# LightingUPS_v4-1.net
KiCad netlist of a schematic drawn in EAGLE
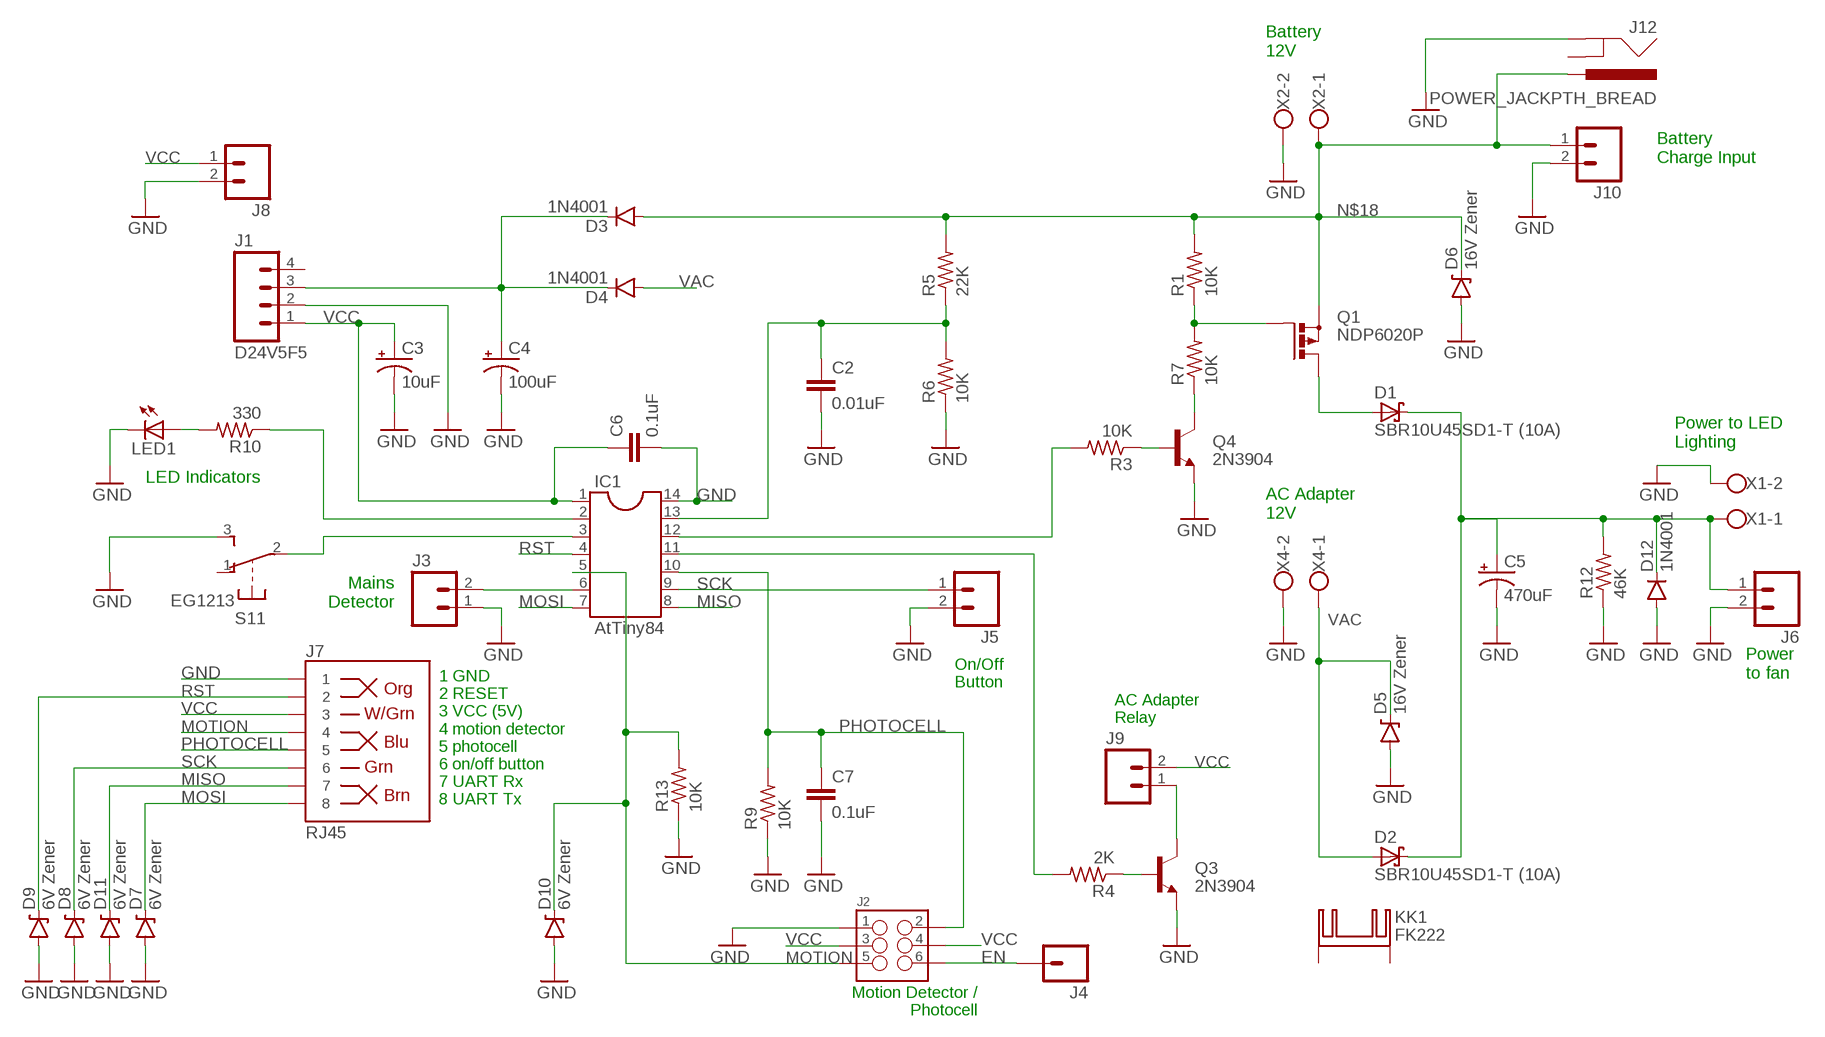
[diagram p0: schematic, sheet 1]

(export (version "E")
  (design (tool "Eeschema 10.0.6"))
  (components
    (comp (ref "C2")
      (value "0.01uF")
      (footprint "eagle-import:CAP-PTH-5MM")
      (libsource (lib "eagle-import") (part "SparkFun-Passives_CAPPTH1"))
    )
    (comp (ref "C3")
      (value "10uF")
      (footprint "eagle-import:CPOL-RADIAL-100UF-25V")
      (libsource (lib "eagle-import") (part "CAP_POLPTH1"))
    )
    (comp (ref "C4")
      (value "100uF")
      (footprint "eagle-import:CPOL-RADIAL-100UF-25V")
      (libsource (lib "eagle-import") (part "CAP_POLPTH1"))
    )
    (comp (ref "C5")
      (value "470uF")
      (footprint "eagle-import:CPOL-RADIAL-1000UF-25V")
      (libsource (lib "eagle-import") (part "CAP_POLPTH4"))
    )
    (comp (ref "C6")
      (value "0.1uF")
      (footprint "eagle-import:CAP-PTH-SMALL")
      (libsource (lib "eagle-import") (part "CAPPTH"))
    )
    (comp (ref "C7")
      (value "0.1uF")
      (footprint "eagle-import:CAP-PTH-SMALL")
      (libsource (lib "eagle-import") (part "CAPPTH"))
    )
    (comp (ref "D1")
      (value "SBR10U45SD1-T (10A)")
      (footprint "eagle-import:DO201T15")
      (libsource (lib "eagle-import") (part "SCHOTTKY-DIODEDO201T15"))
    )
    (comp (ref "D2")
      (value "SBR10U45SD1-T (10A)")
      (footprint "eagle-import:DO201T15")
      (libsource (lib "eagle-import") (part "SCHOTTKY-DIODEDO201T15"))
    )
    (comp (ref "D3")
      (value "1N4001")
      (footprint "eagle-import:DIODE-1N4001")
      (libsource (lib "eagle-import") (part "DIODEPTH"))
    )
    (comp (ref "D4")
      (value "1N4001")
      (footprint "eagle-import:DIODE-1N4001")
      (libsource (lib "eagle-import") (part "DIODEPTH"))
    )
    (comp (ref "D5")
      (value "16V Zener")
      (footprint "eagle-import:DIODE-ZENER")
      (libsource (lib "eagle-import") (part "DIODE-ZENERPTH"))
    )
    (comp (ref "D6")
      (value "16V Zener")
      (footprint "eagle-import:DIODE-ZENER")
      (libsource (lib "eagle-import") (part "DIODE-ZENERPTH"))
    )
    (comp (ref "D7")
      (value "6V Zener")
      (footprint "eagle-import:DIODE-ZENER")
      (libsource (lib "eagle-import") (part "DIODE-ZENERPTH"))
    )
    (comp (ref "D8")
      (value "6V Zener")
      (footprint "eagle-import:DIODE-ZENER")
      (libsource (lib "eagle-import") (part "DIODE-ZENERPTH"))
    )
    (comp (ref "D9")
      (value "6V Zener")
      (footprint "eagle-import:DIODE-ZENER")
      (libsource (lib "eagle-import") (part "DIODE-ZENERPTH"))
    )
    (comp (ref "D10")
      (value "6V Zener")
      (footprint "eagle-import:DIODE-ZENER")
      (libsource (lib "eagle-import") (part "DIODE-ZENERPTH"))
    )
    (comp (ref "D11")
      (value "6V Zener")
      (footprint "eagle-import:DIODE-ZENER")
      (libsource (lib "eagle-import") (part "DIODE-ZENERPTH"))
    )
    (comp (ref "D12")
      (value "1N4001")
      (footprint "eagle-import:DIODE-1N4001")
      (libsource (lib "eagle-import") (part "DIODEPTH"))
    )
    (comp (ref "IC1")
      (value "AtTiny84")
      (footprint "eagle-import:DIL14")
      (libsource (lib "eagle-import") (part "DIL14"))
    )
    (comp (ref "J1")
      (value "D24V5F5")
      (footprint "eagle-import:1X04")
      (libsource (lib "eagle-import") (part "M04PTH"))
    )
    (comp (ref "J2")
      (value "M03X2SHROUD")
      (footprint "eagle-import:2X3-SHROUDED")
      (libsource (lib "eagle-import") (part "M03X2SHROUD"))
    )
    (comp (ref "J3")
      (value "M02PTH")
      (footprint "eagle-import:1X02")
      (libsource (lib "eagle-import") (part "M02PTH"))
    )
    (comp (ref "J4")
      (value "M01PTH")
      (footprint "eagle-import:1X01")
      (libsource (lib "eagle-import") (part "M01PTH"))
    )
    (comp (ref "J5")
      (value "M02PTH")
      (footprint "eagle-import:1X02")
      (libsource (lib "eagle-import") (part "M02PTH"))
    )
    (comp (ref "J6")
      (value "M02PTH")
      (footprint "eagle-import:1X02")
      (libsource (lib "eagle-import") (part "M02PTH"))
    )
    (comp (ref "J7")
      (value "RJ45")
      (footprint "eagle-import:RJ45-8")
      (libsource (lib "eagle-import") (part "RJ45-8PTH"))
    )
    (comp (ref "J8")
      (value "M02PTH")
      (footprint "eagle-import:1X02")
      (libsource (lib "eagle-import") (part "M02PTH"))
    )
    (comp (ref "J9")
      (value "M02PTH")
      (footprint "eagle-import:1X02")
      (libsource (lib "eagle-import") (part "M02PTH"))
    )
    (comp (ref "J10")
      (value "M02PTH")
      (footprint "eagle-import:1X02")
      (libsource (lib "eagle-import") (part "M02PTH"))
    )
    (comp (ref "J12")
      (value "POWER_JACKPTH_BREAD")
      (footprint "eagle-import:POWER_JACK_PTH_BREAD")
      (libsource (lib "eagle-import") (part "POWER_JACKPTH_BREAD"))
    )
    (comp (ref "KK1")
      (value "FK222")
      (footprint "eagle-import:FK222")
      (libsource (lib "eagle-import") (part "FK222"))
    )
    (comp (ref "LED1")
      (value "LED5MM")
      (footprint "eagle-import:LED5MM")
      (libsource (lib "eagle-import") (part "LED5MM"))
    )
    (comp (ref "Q1")
      (value "NDP6020P")
      (footprint "eagle-import:TO220BV")
      (libsource (lib "eagle-import") (part "PMOSFET_PTO220BV"))
    )
    (comp (ref "Q3")
      (value "2N3904")
      (footprint "eagle-import:TO-92-AMMO")
      (libsource (lib "eagle-import") (part "TRANSISTOR_NPNTO-92-AMMO"))
    )
    (comp (ref "Q4")
      (value "2N3904")
      (footprint "eagle-import:TO-92-AMMO")
      (libsource (lib "eagle-import") (part "TRANSISTOR_NPNTO-92-AMMO"))
    )
    (comp (ref "R1")
      (value "10K")
      (footprint "eagle-import:0204_5")
      (libsource (lib "eagle-import") (part "R-US_0204/5"))
    )
    (comp (ref "R3")
      (value "10K")
      (footprint "eagle-import:0204_5")
      (libsource (lib "eagle-import") (part "R-US_0204/5"))
    )
    (comp (ref "R4")
      (value "2K")
      (footprint "eagle-import:0204_5")
      (libsource (lib "eagle-import") (part "R-US_0204/5"))
    )
    (comp (ref "R5")
      (value "22K")
      (footprint "eagle-import:0204_5")
      (libsource (lib "eagle-import") (part "R-US_0204/5"))
    )
    (comp (ref "R6")
      (value "10K")
      (footprint "eagle-import:0204_5")
      (libsource (lib "eagle-import") (part "R-US_0204/5"))
    )
    (comp (ref "R7")
      (value "10K")
      (footprint "eagle-import:0204_5")
      (libsource (lib "eagle-import") (part "R-US_0204/5"))
    )
    (comp (ref "R9")
      (value "10K")
      (footprint "eagle-import:0204_5")
      (libsource (lib "eagle-import") (part "R-US_0204/5"))
    )
    (comp (ref "R10")
      (value "330")
      (footprint "eagle-import:0204_5")
      (libsource (lib "eagle-import") (part "R-US_0204/5"))
    )
    (comp (ref "R12")
      (value "46K")
      (footprint "eagle-import:0204_5")
      (libsource (lib "eagle-import") (part "R-US_0204/5"))
    )
    (comp (ref "R13")
      (value "10K")
      (footprint "eagle-import:0204_5")
      (libsource (lib "eagle-import") (part "R-US_0204/5"))
    )
    (comp (ref "S1")
      (value "EG1213")
      (footprint "eagle-import:EG1213")
      (libsource (lib "eagle-import") (part "EG1213"))
    )
    (comp (ref "X1")
      (value "W237-102")
      (footprint "eagle-import:W237-102")
      (fields (field (name "MPN") "237-102"))
      (libsource (lib "eagle-import") (part "W237-102"))
    )
    (comp (ref "X2")
      (value "W237-102")
      (footprint "eagle-import:W237-102")
      (fields (field (name "MPN") "237-102"))
      (libsource (lib "eagle-import") (part "W237-102"))
    )
    (comp (ref "X4")
      (value "W237-102")
      (footprint "eagle-import:W237-102")
      (fields (field (name "MPN") "237-102"))
      (libsource (lib "eagle-import") (part "W237-102"))
    )
  )
  (nets
    (net (code "1") (name "/EN") (class "Default")
      (node (ref "J2") (pin "6") (pinfunction "6_6") (pintype "bidirectional"))
      (node (ref "J4") (pin "1") (pinfunction "1_1") (pintype "passive"))
    )
    (net (code "2") (name "/MISO") (class "Default")
      (node (ref "D11") (pin "P$1") (pinfunction "C_P$1") (pintype "passive"))
      (node (ref "IC1") (pin "8") (pinfunction "8_8") (pintype "passive"))
      (node (ref "J7") (pin "7") (pinfunction "7_7") (pintype "bidirectional"))
    )
    (net (code "3") (name "/MOSI") (class "Default")
      (node (ref "D7") (pin "P$1") (pinfunction "C_P$1") (pintype "passive"))
      (node (ref "IC1") (pin "7") (pinfunction "7_7") (pintype "passive"))
      (node (ref "J7") (pin "8") (pinfunction "8_8") (pintype "bidirectional"))
    )
    (net (code "4") (name "/MOTION") (class "Default")
      (node (ref "D10") (pin "P$1") (pinfunction "C_P$1") (pintype "passive"))
      (node (ref "IC1") (pin "5") (pinfunction "5_5") (pintype "passive"))
      (node (ref "J2") (pin "5") (pinfunction "5_5") (pintype "bidirectional"))
      (node (ref "J7") (pin "4") (pinfunction "4_4") (pintype "bidirectional"))
      (node (ref "R13") (pin "2") (pinfunction "2_2") (pintype "passive"))
    )
    (net (code "5") (name "/N$18") (class "Default")
      (node (ref "D3") (pin "A") (pinfunction "A_A") (pintype "passive"))
      (node (ref "D6") (pin "P$1") (pinfunction "C_P$1") (pintype "passive"))
      (node (ref "J10") (pin "1") (pinfunction "1_1") (pintype "passive"))
      (node (ref "J12") (pin "PWR") (pinfunction "PWR_PWR") (pintype "bidirectional"))
      (node (ref "Q1") (pin "S") (pinfunction "S_S") (pintype "passive"))
      (node (ref "R1") (pin "2") (pinfunction "2_2") (pintype "passive"))
      (node (ref "R5") (pin "2") (pinfunction "2_2") (pintype "passive"))
      (node (ref "X2") (pin "1") (pinfunction "KL_1") (pintype "passive"))
    )
    (net (code "6") (name "/PHOTOCELL") (class "Default")
      (node (ref "C7") (pin "1") (pinfunction "1_1") (pintype "passive"))
      (node (ref "IC1") (pin "10") (pinfunction "10_10") (pintype "passive"))
      (node (ref "J2") (pin "2") (pinfunction "2_2") (pintype "bidirectional"))
      (node (ref "J7") (pin "5") (pinfunction "5_5") (pintype "bidirectional"))
      (node (ref "R9") (pin "2") (pinfunction "2_2") (pintype "passive"))
    )
    (net (code "7") (name "/RST") (class "Default")
      (node (ref "D9") (pin "P$1") (pinfunction "C_P$1") (pintype "passive"))
      (node (ref "IC1") (pin "4") (pinfunction "4_4") (pintype "passive"))
      (node (ref "J7") (pin "2") (pinfunction "2_2") (pintype "bidirectional"))
    )
    (net (code "8") (name "/SCK") (class "Default")
      (node (ref "D8") (pin "P$1") (pinfunction "C_P$1") (pintype "passive"))
      (node (ref "IC1") (pin "9") (pinfunction "9_9") (pintype "passive"))
      (node (ref "J5") (pin "1") (pinfunction "1_1") (pintype "passive"))
      (node (ref "J7") (pin "6") (pinfunction "6_6") (pintype "bidirectional"))
    )
    (net (code "9") (name "/VAC") (class "Default")
      (node (ref "D2") (pin "A") (pinfunction "A_A") (pintype "passive"))
      (node (ref "D4") (pin "A") (pinfunction "A_A") (pintype "passive"))
      (node (ref "D5") (pin "P$1") (pinfunction "C_P$1") (pintype "passive"))
      (node (ref "X4") (pin "1") (pinfunction "KL_1") (pintype "passive"))
    )
    (net (code "10") (name "/VCC") (class "Default")
      (node (ref "C3") (pin "1") (pinfunction "+_1") (pintype "passive"))
      (node (ref "C6") (pin "1") (pinfunction "1_1") (pintype "passive"))
      (node (ref "IC1") (pin "1") (pinfunction "1_1") (pintype "passive"))
      (node (ref "J1") (pin "1") (pinfunction "1_1") (pintype "passive"))
      (node (ref "J2") (pin "3") (pinfunction "3_3") (pintype "bidirectional"))
      (node (ref "J2") (pin "4") (pinfunction "4_4") (pintype "bidirectional"))
      (node (ref "J7") (pin "3") (pinfunction "3_3") (pintype "bidirectional"))
      (node (ref "J8") (pin "1") (pinfunction "1_1") (pintype "passive"))
      (node (ref "J9") (pin "2") (pinfunction "2_2") (pintype "passive"))
    )
    (net (code "11") (name "GND") (class "Default")
      (node (ref "C2") (pin "2") (pinfunction "2_2") (pintype "passive"))
      (node (ref "C3") (pin "2") (pinfunction "-_2") (pintype "passive"))
      (node (ref "C4") (pin "2") (pinfunction "-_2") (pintype "passive"))
      (node (ref "C5") (pin "-") (pinfunction "-_-") (pintype "passive"))
      (node (ref "C6") (pin "2") (pinfunction "2_2") (pintype "passive"))
      (node (ref "C7") (pin "2") (pinfunction "2_2") (pintype "passive"))
      (node (ref "D10") (pin "P$2") (pinfunction "A_P$2") (pintype "passive"))
      (node (ref "D11") (pin "P$2") (pinfunction "A_P$2") (pintype "passive"))
      (node (ref "D12") (pin "A") (pinfunction "A_A") (pintype "passive"))
      (node (ref "D5") (pin "P$2") (pinfunction "A_P$2") (pintype "passive"))
      (node (ref "D6") (pin "P$2") (pinfunction "A_P$2") (pintype "passive"))
      (node (ref "D7") (pin "P$2") (pinfunction "A_P$2") (pintype "passive"))
      (node (ref "D8") (pin "P$2") (pinfunction "A_P$2") (pintype "passive"))
      (node (ref "D9") (pin "P$2") (pinfunction "A_P$2") (pintype "passive"))
      (node (ref "IC1") (pin "14") (pinfunction "14_14") (pintype "passive"))
      (node (ref "J1") (pin "2") (pinfunction "2_2") (pintype "passive"))
      (node (ref "J10") (pin "2") (pinfunction "2_2") (pintype "passive"))
      (node (ref "J12") (pin "GND") (pinfunction "GND_GND") (pintype "bidirectional"))
      (node (ref "J2") (pin "1") (pinfunction "1_1") (pintype "bidirectional"))
      (node (ref "J3") (pin "1") (pinfunction "1_1") (pintype "passive"))
      (node (ref "J5") (pin "2") (pinfunction "2_2") (pintype "passive"))
      (node (ref "J6") (pin "2") (pinfunction "2_2") (pintype "passive"))
      (node (ref "J7") (pin "1") (pinfunction "1_1") (pintype "bidirectional"))
      (node (ref "J8") (pin "2") (pinfunction "2_2") (pintype "passive"))
      (node (ref "LED1") (pin "K") (pinfunction "C_K") (pintype "passive"))
      (node (ref "Q3") (pin "1") (pinfunction "E_1") (pintype "passive"))
      (node (ref "Q4") (pin "1") (pinfunction "E_1") (pintype "passive"))
      (node (ref "R12") (pin "1") (pinfunction "1_1") (pintype "passive"))
      (node (ref "R13") (pin "1") (pinfunction "1_1") (pintype "passive"))
      (node (ref "R6") (pin "1") (pinfunction "1_1") (pintype "passive"))
      (node (ref "R9") (pin "1") (pinfunction "1_1") (pintype "passive"))
      (node (ref "S1") (pin "3") (pinfunction "S_3") (pintype "passive"))
      (node (ref "X1") (pin "2") (pinfunction "KL_2") (pintype "passive"))
      (node (ref "X2") (pin "2") (pinfunction "KL_2") (pintype "passive"))
      (node (ref "X4") (pin "2") (pinfunction "KL_2") (pintype "passive"))
    )
    (net (code "12") (name "Net-(C2-Pad1)") (class "Default")
      (node (ref "C2") (pin "1") (pinfunction "1_1") (pintype "passive"))
      (node (ref "IC1") (pin "13") (pinfunction "13_13") (pintype "passive"))
      (node (ref "R5") (pin "1") (pinfunction "1_1") (pintype "passive"))
      (node (ref "R6") (pin "2") (pinfunction "2_2") (pintype "passive"))
    )
    (net (code "13") (name "Net-(C4-+)") (class "Default")
      (node (ref "C4") (pin "1") (pinfunction "+_1") (pintype "passive"))
      (node (ref "D3") (pin "C") (pinfunction "C_C") (pintype "passive"))
      (node (ref "D4") (pin "C") (pinfunction "C_C") (pintype "passive"))
      (node (ref "J1") (pin "3") (pinfunction "3_3") (pintype "passive"))
    )
    (net (code "14") (name "Net-(D1-PadA)") (class "Default")
      (node (ref "D1") (pin "A") (pinfunction "A_A") (pintype "passive"))
      (node (ref "Q1") (pin "D") (pinfunction "D_D") (pintype "passive"))
    )
    (net (code "15") (name "Net-(IC1-Pad2)") (class "Default")
      (node (ref "IC1") (pin "2") (pinfunction "2_2") (pintype "passive"))
      (node (ref "R10") (pin "1") (pinfunction "1_1") (pintype "passive"))
    )
    (net (code "16") (name "Net-(IC1-Pad6)") (class "Default")
      (node (ref "IC1") (pin "6") (pinfunction "6_6") (pintype "passive"))
      (node (ref "J3") (pin "2") (pinfunction "2_2") (pintype "passive"))
    )
    (net (code "17") (name "Net-(IC1-Pad11)") (class "Default")
      (node (ref "IC1") (pin "11") (pinfunction "11_11") (pintype "passive"))
      (node (ref "R4") (pin "2") (pinfunction "2_2") (pintype "passive"))
    )
    (net (code "18") (name "Net-(IC1-Pad12)") (class "Default")
      (node (ref "IC1") (pin "12") (pinfunction "12_12") (pintype "passive"))
      (node (ref "R3") (pin "2") (pinfunction "2_2") (pintype "passive"))
    )
    (net (code "19") (name "Net-(LED1-PadA)") (class "Default")
      (node (ref "LED1") (pin "A") (pinfunction "A_A") (pintype "passive"))
      (node (ref "R10") (pin "2") (pinfunction "2_2") (pintype "passive"))
    )
    (net (code "20") (name "Net-(Q1-PadG)") (class "Default")
      (node (ref "Q1") (pin "G") (pinfunction "G_G") (pintype "passive"))
      (node (ref "R1") (pin "1") (pinfunction "1_1") (pintype "passive"))
      (node (ref "R7") (pin "2") (pinfunction "2_2") (pintype "passive"))
    )
    (net (code "21") (name "Net-(Q3-B)") (class "Default")
      (node (ref "Q3") (pin "2") (pinfunction "B_2") (pintype "passive"))
      (node (ref "R4") (pin "1") (pinfunction "1_1") (pintype "passive"))
    )
    (net (code "22") (name "Net-(Q3-C)") (class "Default")
      (node (ref "J9") (pin "1") (pinfunction "1_1") (pintype "passive"))
      (node (ref "Q3") (pin "3") (pinfunction "C_3") (pintype "passive"))
    )
    (net (code "23") (name "Net-(Q4-B)") (class "Default")
      (node (ref "Q4") (pin "2") (pinfunction "B_2") (pintype "passive"))
      (node (ref "R3") (pin "1") (pinfunction "1_1") (pintype "passive"))
    )
    (net (code "24") (name "Net-(Q4-C)") (class "Default")
      (node (ref "Q4") (pin "3") (pinfunction "C_3") (pintype "passive"))
      (node (ref "R7") (pin "1") (pinfunction "1_1") (pintype "passive"))
    )
    (net (code "25") (name "Net-(S1A-P)") (class "Default")
      (node (ref "IC1") (pin "3") (pinfunction "3_3") (pintype "passive"))
      (node (ref "S1") (pin "2") (pinfunction "P_2") (pintype "passive"))
    )
    (net (code "26") (name "Net-(X1A-KL)") (class "Default")
      (node (ref "C5") (pin "+") (pinfunction "+_+") (pintype "passive"))
      (node (ref "D1") (pin "C") (pinfunction "C_C") (pintype "passive"))
      (node (ref "D12") (pin "C") (pinfunction "C_C") (pintype "passive"))
      (node (ref "D2") (pin "C") (pinfunction "C_C") (pintype "passive"))
      (node (ref "J6") (pin "1") (pinfunction "1_1") (pintype "passive"))
      (node (ref "R12") (pin "2") (pinfunction "2_2") (pintype "passive"))
      (node (ref "X1") (pin "1") (pinfunction "KL_1") (pintype "passive"))
    )
    (net (code "27") (name "unconnected-(J1-Pad4)") (class "Default")
      (node (ref "J1") (pin "4") (pinfunction "4_4") (pintype "passive"))
    )
    (net (code "28") (name "unconnected-(J12-PadGNDBREAK)") (class "Default")
      (node (ref "J12") (pin "GNDBREAK") (pinfunction "GNDBREAK_GNDBREAK") (pintype "bidirectional"))
    )
    (net (code "29") (name "unconnected-(KK1-K-PadA2,8)") (class "Default")
      (node (ref "KK1") (pin "A2,8") (pinfunction "K_A2,8") (pintype "passive"))
    )
    (net (code "30") (name "unconnected-(KK1-K-PadB2,8)") (class "Default")
      (node (ref "KK1") (pin "B2,8") (pinfunction "K_B2,8") (pintype "passive"))
    )
    (net (code "31") (name "unconnected-(S1A-O-Pad1)") (class "Default")
      (node (ref "S1") (pin "1") (pinfunction "O_1") (pintype "passive"))
    )
  )
)
